# waga_can.net
KiCad netlist of a schematic drawn in EAGLE
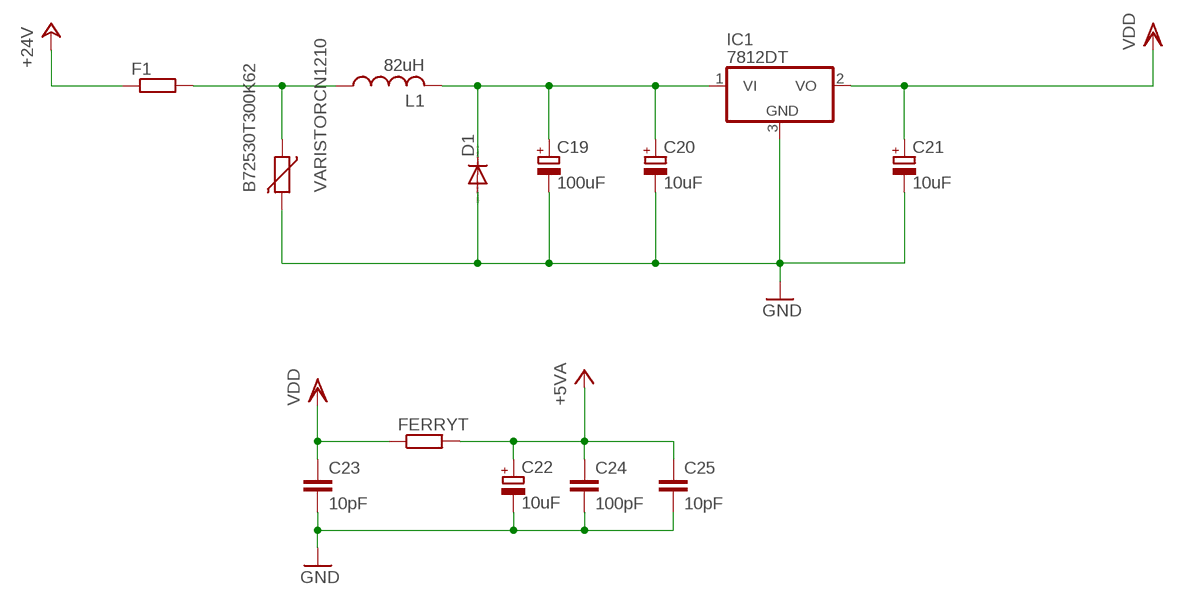
[diagram p0: schematic, sheet 1]
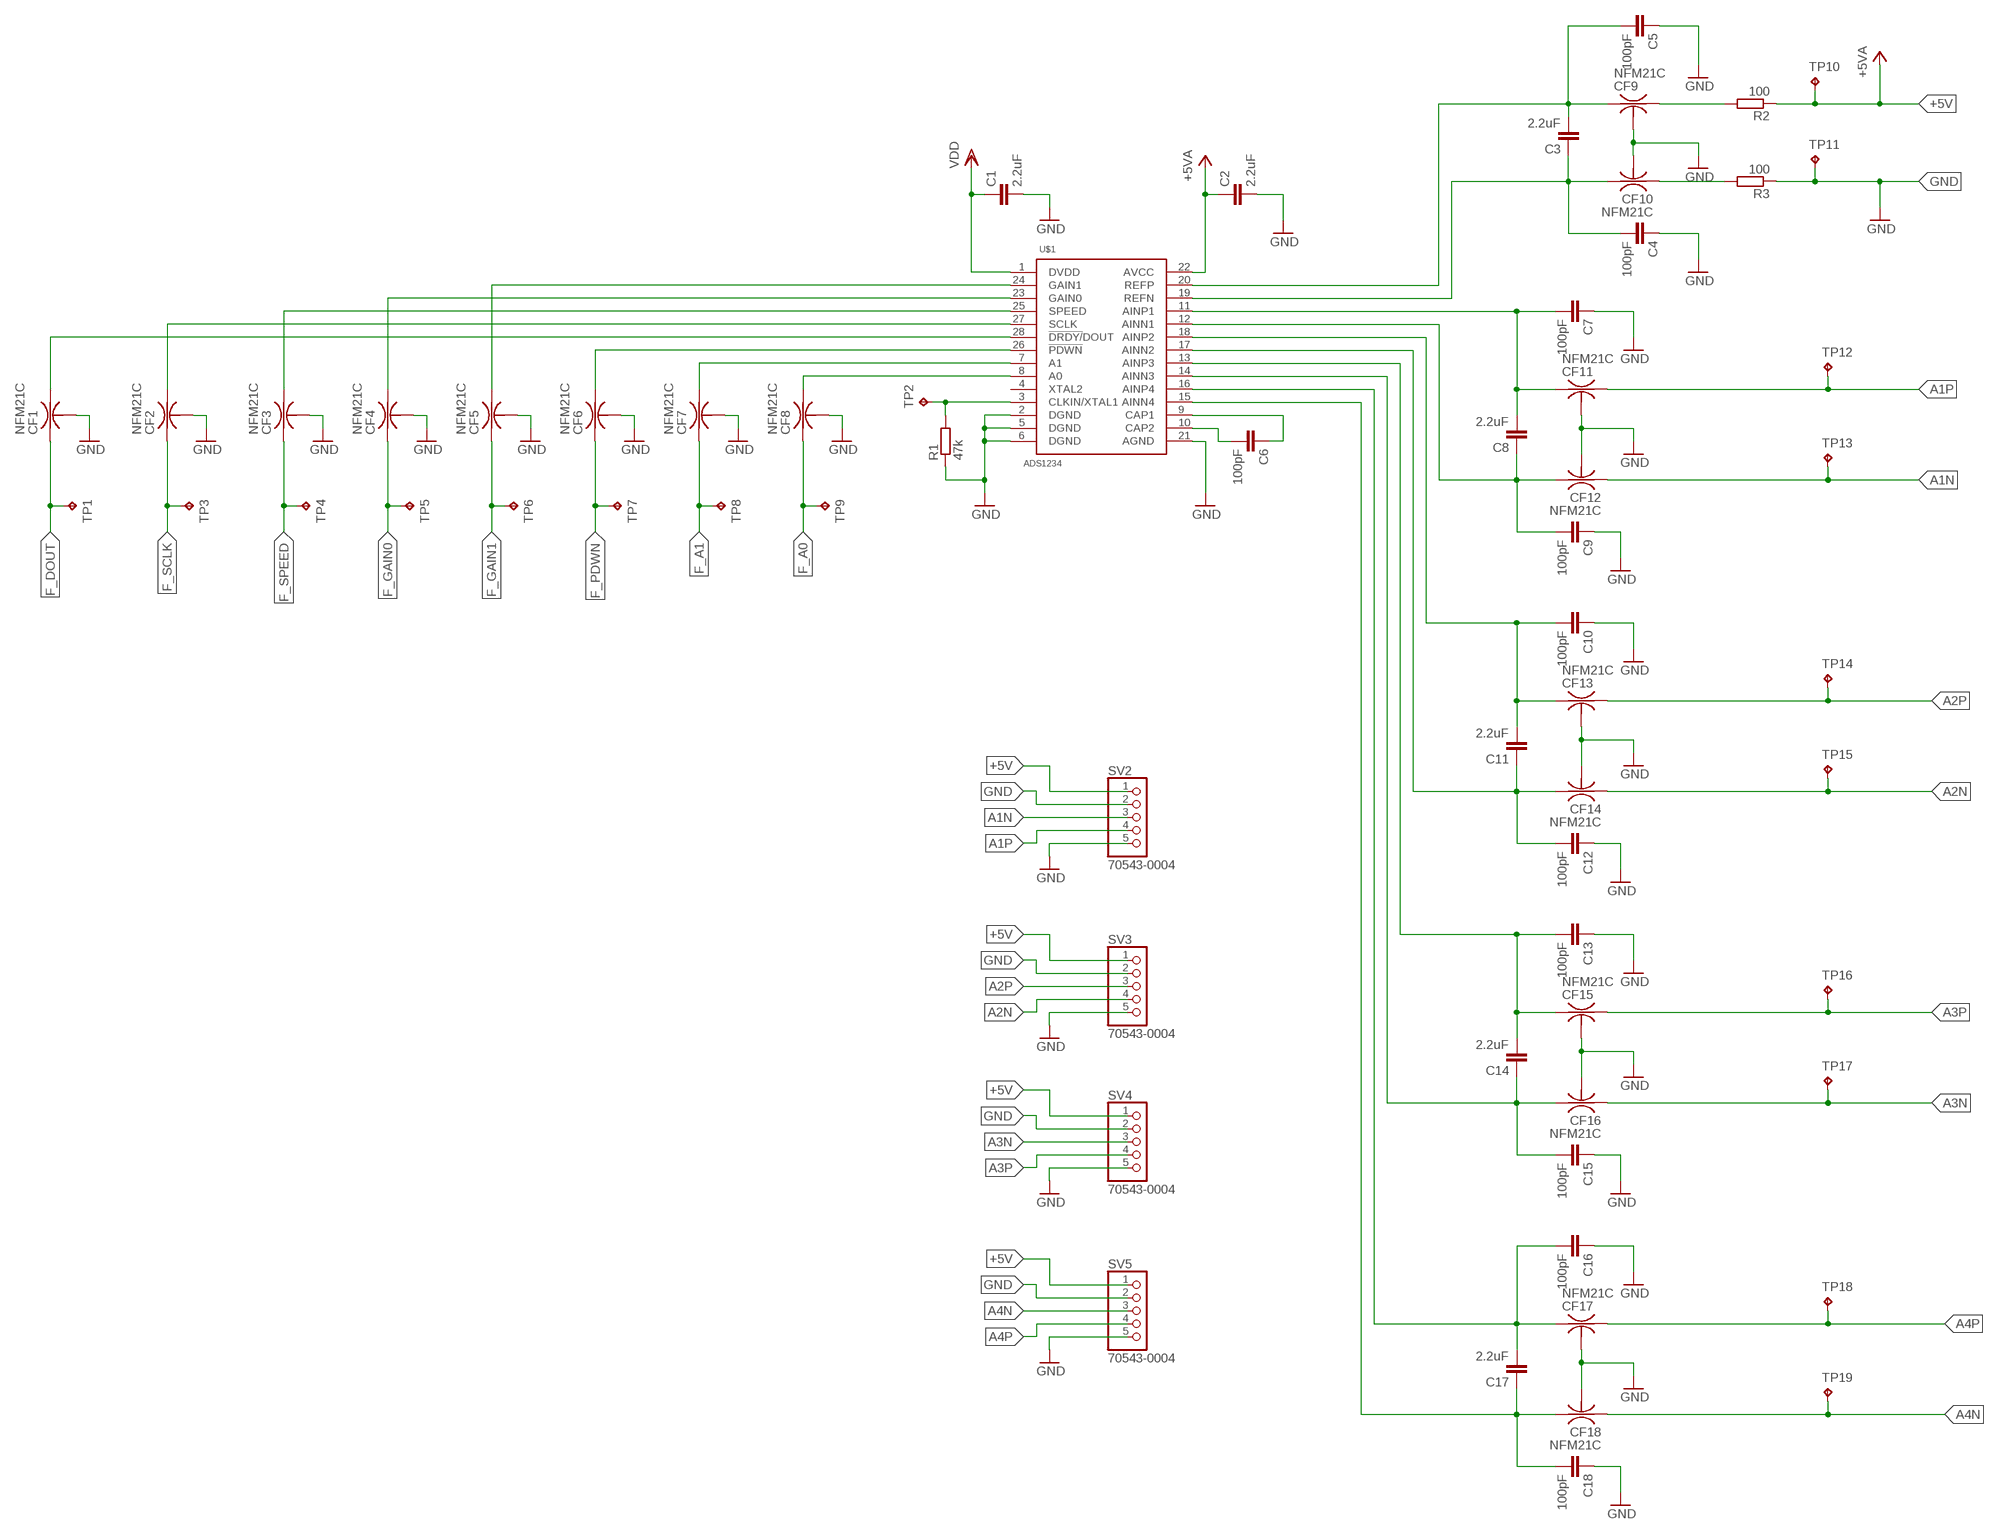
[diagram p1: schematic, sheet 2, part 1 of 2]
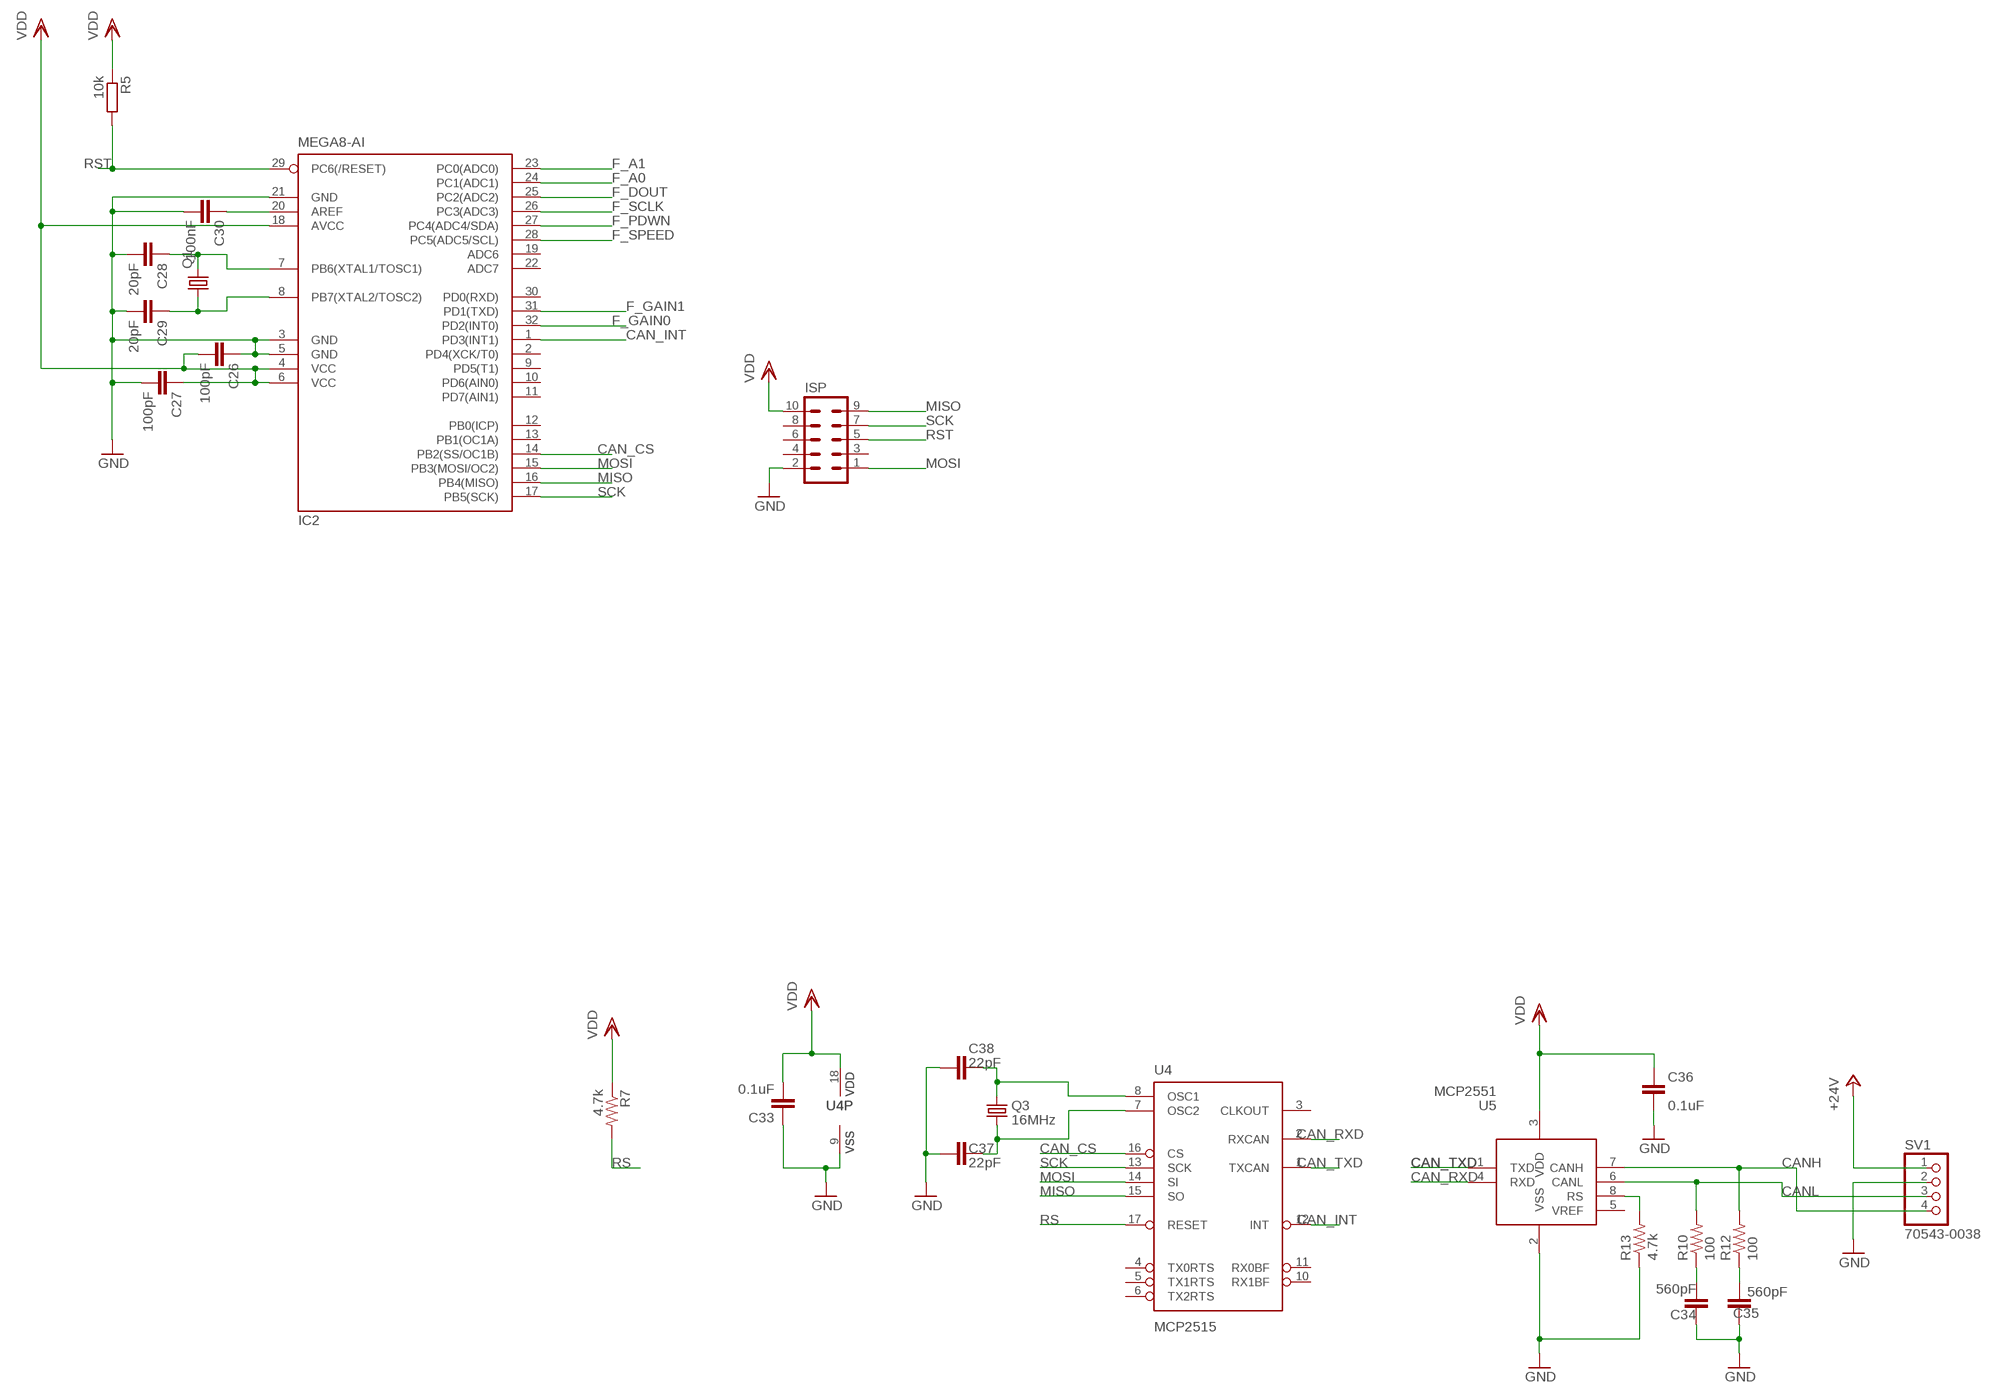
[diagram p2: schematic, sheet 2, part 2 of 2]

(export (version "E")
  (design (tool "Eeschema 10.0.6"))
  (components
    (comp (ref "C1")
      (value "2.2uF")
      (footprint "eagle-import:C0805K")
      (libsource (lib "eagle-import") (part "C-EUC0805K"))
    )
    (comp (ref "C2")
      (value "2.2uF")
      (footprint "eagle-import:C0805K")
      (libsource (lib "eagle-import") (part "C-EUC0805K"))
    )
    (comp (ref "C3")
      (value "2.2uF")
      (footprint "eagle-import:C0805K")
      (libsource (lib "eagle-import") (part "C-EUC0805K"))
    )
    (comp (ref "C4")
      (value "100pF")
      (footprint "eagle-import:C0805K")
      (libsource (lib "eagle-import") (part "C-EUC0805K"))
    )
    (comp (ref "C5")
      (value "100pF")
      (footprint "eagle-import:C0805K")
      (libsource (lib "eagle-import") (part "C-EUC0805K"))
    )
    (comp (ref "C6")
      (value "100pF")
      (footprint "eagle-import:C0805K")
      (libsource (lib "eagle-import") (part "C-EUC0805K"))
    )
    (comp (ref "C7")
      (value "100pF")
      (footprint "eagle-import:C0805K")
      (libsource (lib "eagle-import") (part "C-EUC0805K"))
    )
    (comp (ref "C8")
      (value "2.2uF")
      (footprint "eagle-import:C0805K")
      (libsource (lib "eagle-import") (part "C-EUC0805K"))
    )
    (comp (ref "C9")
      (value "100pF")
      (footprint "eagle-import:C0805K")
      (libsource (lib "eagle-import") (part "C-EUC0805K"))
    )
    (comp (ref "C10")
      (value "100pF")
      (footprint "eagle-import:C0805K")
      (libsource (lib "eagle-import") (part "C-EUC0805K"))
    )
    (comp (ref "C11")
      (value "2.2uF")
      (footprint "eagle-import:C0805K")
      (libsource (lib "eagle-import") (part "C-EUC0805K"))
    )
    (comp (ref "C12")
      (value "100pF")
      (footprint "eagle-import:C0805K")
      (libsource (lib "eagle-import") (part "C-EUC0805K"))
    )
    (comp (ref "C13")
      (value "100pF")
      (footprint "eagle-import:C0805K")
      (libsource (lib "eagle-import") (part "C-EUC0805K"))
    )
    (comp (ref "C14")
      (value "2.2uF")
      (footprint "eagle-import:C0805K")
      (libsource (lib "eagle-import") (part "C-EUC0805K"))
    )
    (comp (ref "C15")
      (value "100pF")
      (footprint "eagle-import:C0805K")
      (libsource (lib "eagle-import") (part "C-EUC0805K"))
    )
    (comp (ref "C16")
      (value "100pF")
      (footprint "eagle-import:C0805K")
      (libsource (lib "eagle-import") (part "C-EUC0805K"))
    )
    (comp (ref "C17")
      (value "2.2uF")
      (footprint "eagle-import:C0805K")
      (libsource (lib "eagle-import") (part "C-EUC0805K"))
    )
    (comp (ref "C18")
      (value "100pF")
      (footprint "eagle-import:C0805K")
      (libsource (lib "eagle-import") (part "C-EUC0805K"))
    )
    (comp (ref "C26")
      (value "100pF")
      (footprint "eagle-import:C0805K")
      (libsource (lib "eagle-import") (part "C-EUC0805K"))
    )
    (comp (ref "C27")
      (value "100pF")
      (footprint "eagle-import:C0805K")
      (libsource (lib "eagle-import") (part "C-EUC0805K"))
    )
    (comp (ref "C28")
      (value "20pF")
      (footprint "eagle-import:C0805K")
      (libsource (lib "eagle-import") (part "C-EUC0805K"))
    )
    (comp (ref "C29")
      (value "20pF")
      (footprint "eagle-import:C0805K")
      (libsource (lib "eagle-import") (part "C-EUC0805K"))
    )
    (comp (ref "C30")
      (value "100nF")
      (footprint "eagle-import:C0805K")
      (libsource (lib "eagle-import") (part "C-EUC0805K"))
    )
    (comp (ref "C33")
      (value "0.1uF")
      (footprint "eagle-import:0603-CAP")
      (libsource (lib "eagle-import") (part "CAP0603-CAP"))
    )
    (comp (ref "C34")
      (value "560pF")
      (footprint "eagle-import:0603-CAP")
      (libsource (lib "eagle-import") (part "CAP0603-CAP"))
    )
    (comp (ref "C35")
      (value "560pF")
      (footprint "eagle-import:0603-CAP")
      (libsource (lib "eagle-import") (part "CAP0603-CAP"))
    )
    (comp (ref "C36")
      (value "0.1uF")
      (footprint "eagle-import:0603-CAP")
      (libsource (lib "eagle-import") (part "CAP0603-CAP"))
    )
    (comp (ref "C37")
      (value "22pF")
      (footprint "eagle-import:0603-CAP")
      (libsource (lib "eagle-import") (part "CAP0603-CAP"))
    )
    (comp (ref "C38")
      (value "22pF")
      (footprint "eagle-import:0603-CAP")
      (libsource (lib "eagle-import") (part "CAP0603-CAP"))
    )
    (comp (ref "CF1")
      (value "NFM21C")
      (footprint "eagle-import:NFM21C")
      (fields (field (name "MPN") "NFM21CC102R1H3D"))
      (libsource (lib "eagle-import") (part "NFM21C"))
    )
    (comp (ref "CF2")
      (value "NFM21C")
      (footprint "eagle-import:NFM21C")
      (fields (field (name "MPN") "NFM21CC102R1H3D"))
      (libsource (lib "eagle-import") (part "NFM21C"))
    )
    (comp (ref "CF3")
      (value "NFM21C")
      (footprint "eagle-import:NFM21C")
      (fields (field (name "MPN") "NFM21CC102R1H3D"))
      (libsource (lib "eagle-import") (part "NFM21C"))
    )
    (comp (ref "CF4")
      (value "NFM21C")
      (footprint "eagle-import:NFM21C")
      (fields (field (name "MPN") "NFM21CC102R1H3D"))
      (libsource (lib "eagle-import") (part "NFM21C"))
    )
    (comp (ref "CF5")
      (value "NFM21C")
      (footprint "eagle-import:NFM21C")
      (fields (field (name "MPN") "NFM21CC102R1H3D"))
      (libsource (lib "eagle-import") (part "NFM21C"))
    )
    (comp (ref "CF6")
      (value "NFM21C")
      (footprint "eagle-import:NFM21C")
      (fields (field (name "MPN") "NFM21CC102R1H3D"))
      (libsource (lib "eagle-import") (part "NFM21C"))
    )
    (comp (ref "CF7")
      (value "NFM21C")
      (footprint "eagle-import:NFM21C")
      (fields (field (name "MPN") "NFM21CC102R1H3D"))
      (libsource (lib "eagle-import") (part "NFM21C"))
    )
    (comp (ref "CF8")
      (value "NFM21C")
      (footprint "eagle-import:NFM21C")
      (fields (field (name "MPN") "NFM21CC102R1H3D"))
      (libsource (lib "eagle-import") (part "NFM21C"))
    )
    (comp (ref "CF9")
      (value "NFM21C")
      (footprint "eagle-import:NFM21C")
      (fields (field (name "MPN") "NFM21CC102R1H3D"))
      (libsource (lib "eagle-import") (part "NFM21C"))
    )
    (comp (ref "CF10")
      (value "NFM21C")
      (footprint "eagle-import:NFM21C")
      (fields (field (name "MPN") "NFM21CC102R1H3D"))
      (libsource (lib "eagle-import") (part "NFM21C"))
    )
    (comp (ref "CF11")
      (value "NFM21C")
      (footprint "eagle-import:NFM21C")
      (fields (field (name "MPN") "NFM21CC102R1H3D"))
      (libsource (lib "eagle-import") (part "NFM21C"))
    )
    (comp (ref "CF12")
      (value "NFM21C")
      (footprint "eagle-import:NFM21C")
      (fields (field (name "MPN") "NFM21CC102R1H3D"))
      (libsource (lib "eagle-import") (part "NFM21C"))
    )
    (comp (ref "CF13")
      (value "NFM21C")
      (footprint "eagle-import:NFM21C")
      (fields (field (name "MPN") "NFM21CC102R1H3D"))
      (libsource (lib "eagle-import") (part "NFM21C"))
    )
    (comp (ref "CF14")
      (value "NFM21C")
      (footprint "eagle-import:NFM21C")
      (fields (field (name "MPN") "NFM21CC102R1H3D"))
      (libsource (lib "eagle-import") (part "NFM21C"))
    )
    (comp (ref "CF15")
      (value "NFM21C")
      (footprint "eagle-import:NFM21C")
      (fields (field (name "MPN") "NFM21CC102R1H3D"))
      (libsource (lib "eagle-import") (part "NFM21C"))
    )
    (comp (ref "CF16")
      (value "NFM21C")
      (footprint "eagle-import:NFM21C")
      (fields (field (name "MPN") "NFM21CC102R1H3D"))
      (libsource (lib "eagle-import") (part "NFM21C"))
    )
    (comp (ref "CF17")
      (value "NFM21C")
      (footprint "eagle-import:NFM21C")
      (fields (field (name "MPN") "NFM21CC102R1H3D"))
      (libsource (lib "eagle-import") (part "NFM21C"))
    )
    (comp (ref "CF18")
      (value "NFM21C")
      (footprint "eagle-import:NFM21C")
      (fields (field (name "MPN") "NFM21CC102R1H3D"))
      (libsource (lib "eagle-import") (part "NFM21C"))
    )
    (comp (ref "IC2")
      (value "MEGA8-AI")
      (footprint "eagle-import:TQFP32-08")
      (fields (field (name "MPN") "ATMEGA8-16AU"))
      (libsource (lib "eagle-import") (part "MEGA8-AI"))
    )
    (comp (ref "ISP")
      (value "ML10")
      (footprint "eagle-import:ML10")
      (libsource (lib "eagle-import") (part "ML10"))
    )
    (comp (ref "Q1")
      (value "CRYSTALCTS406")
      (footprint "eagle-import:CTS406")
      (libsource (lib "eagle-import") (part "CRYSTALCTS406"))
    )
    (comp (ref "Q3")
      (value "16MHz")
      (footprint "eagle-import:CRYSTAL-SMD-5X3")
      (libsource (lib "eagle-import") (part "CRYSTAL5X3"))
    )
    (comp (ref "R1")
      (value "47k")
      (footprint "eagle-import:R0805")
      (libsource (lib "eagle-import") (part "R-EU_R0805"))
    )
    (comp (ref "R2")
      (value "100")
      (footprint "eagle-import:R0805")
      (libsource (lib "eagle-import") (part "R-EU_R0805"))
    )
    (comp (ref "R3")
      (value "100")
      (footprint "eagle-import:R0805")
      (libsource (lib "eagle-import") (part "R-EU_R0805"))
    )
    (comp (ref "R5")
      (value "10k")
      (footprint "eagle-import:R0805")
      (libsource (lib "eagle-import") (part "R-EU_R0805"))
    )
    (comp (ref "R7")
      (value "4.7k")
      (footprint "eagle-import:0603-RES")
      (libsource (lib "eagle-import") (part "RESISTOR0603-RES"))
    )
    (comp (ref "R10")
      (value "100")
      (footprint "eagle-import:0603-RES")
      (libsource (lib "eagle-import") (part "RESISTOR0603-RES"))
    )
    (comp (ref "R12")
      (value "100")
      (footprint "eagle-import:0603-RES")
      (libsource (lib "eagle-import") (part "RESISTOR0603-RES"))
    )
    (comp (ref "R13")
      (value "4.7k")
      (footprint "eagle-import:0603-RES")
      (libsource (lib "eagle-import") (part "RESISTOR0603-RES"))
    )
    (comp (ref "SV1")
      (value "70543-0038")
      (footprint "eagle-import:70543-0038")
      (libsource (lib "eagle-import") (part "70543-0038"))
    )
    (comp (ref "SV2")
      (value "70543-0004")
      (footprint "eagle-import:70543-0004")
      (libsource (lib "eagle-import") (part "70543-0004"))
    )
    (comp (ref "SV3")
      (value "70543-0004")
      (footprint "eagle-import:70543-0004")
      (libsource (lib "eagle-import") (part "70543-0004"))
    )
    (comp (ref "SV4")
      (value "70543-0004")
      (footprint "eagle-import:70543-0004")
      (libsource (lib "eagle-import") (part "70543-0004"))
    )
    (comp (ref "SV5")
      (value "70543-0004")
      (footprint "eagle-import:70543-0004")
      (libsource (lib "eagle-import") (part "70543-0004"))
    )
    (comp (ref "TP1")
      (value "TPTP06R")
      (footprint "eagle-import:TP06R")
      (libsource (lib "eagle-import") (part "TPTP06R"))
    )
    (comp (ref "TP2")
      (value "TPTP06R")
      (footprint "eagle-import:TP06R")
      (libsource (lib "eagle-import") (part "TPTP06R"))
    )
    (comp (ref "TP3")
      (value "TPTP06R")
      (footprint "eagle-import:TP06R")
      (libsource (lib "eagle-import") (part "TPTP06R"))
    )
    (comp (ref "TP4")
      (value "TPTP06R")
      (footprint "eagle-import:TP06R")
      (libsource (lib "eagle-import") (part "TPTP06R"))
    )
    (comp (ref "TP5")
      (value "TPTP06R")
      (footprint "eagle-import:TP06R")
      (libsource (lib "eagle-import") (part "TPTP06R"))
    )
    (comp (ref "TP6")
      (value "TPTP06R")
      (footprint "eagle-import:TP06R")
      (libsource (lib "eagle-import") (part "TPTP06R"))
    )
    (comp (ref "TP7")
      (value "TPTP06R")
      (footprint "eagle-import:TP06R")
      (libsource (lib "eagle-import") (part "TPTP06R"))
    )
    (comp (ref "TP8")
      (value "TPTP06R")
      (footprint "eagle-import:TP06R")
      (libsource (lib "eagle-import") (part "TPTP06R"))
    )
    (comp (ref "TP9")
      (value "TPTP06R")
      (footprint "eagle-import:TP06R")
      (libsource (lib "eagle-import") (part "TPTP06R"))
    )
    (comp (ref "TP10")
      (value "TPTP06R")
      (footprint "eagle-import:TP06R")
      (libsource (lib "eagle-import") (part "TPTP06R"))
    )
    (comp (ref "TP11")
      (value "TPTP06R")
      (footprint "eagle-import:TP06R")
      (libsource (lib "eagle-import") (part "TPTP06R"))
    )
    (comp (ref "TP12")
      (value "TPTP06R")
      (footprint "eagle-import:TP06R")
      (libsource (lib "eagle-import") (part "TPTP06R"))
    )
    (comp (ref "TP13")
      (value "TPTP06R")
      (footprint "eagle-import:TP06R")
      (libsource (lib "eagle-import") (part "TPTP06R"))
    )
    (comp (ref "TP14")
      (value "TPTP06R")
      (footprint "eagle-import:TP06R")
      (libsource (lib "eagle-import") (part "TPTP06R"))
    )
    (comp (ref "TP15")
      (value "TPTP06R")
      (footprint "eagle-import:TP06R")
      (libsource (lib "eagle-import") (part "TPTP06R"))
    )
    (comp (ref "TP16")
      (value "TPTP06R")
      (footprint "eagle-import:TP06R")
      (libsource (lib "eagle-import") (part "TPTP06R"))
    )
    (comp (ref "TP17")
      (value "TPTP06R")
      (footprint "eagle-import:TP06R")
      (libsource (lib "eagle-import") (part "TPTP06R"))
    )
    (comp (ref "TP18")
      (value "TPTP06R")
      (footprint "eagle-import:TP06R")
      (libsource (lib "eagle-import") (part "TPTP06R"))
    )
    (comp (ref "TP19")
      (value "TPTP06R")
      (footprint "eagle-import:TP06R")
      (libsource (lib "eagle-import") (part "TPTP06R"))
    )
    (comp (ref "U$1")
      (value "ADS1234")
      (footprint "eagle-import:TSSOP-28")
      (libsource (lib "eagle-import") (part "ADS1234"))
    )
    (comp (ref "U4")
      (value "MCP2515")
      (footprint "eagle-import:SO-18W")
      (libsource (lib "eagle-import") (part "MCP2510SO"))
    )
    (comp (ref "U5")
      (value "MCP2551")
      (footprint "eagle-import:SO-08M")
      (libsource (lib "eagle-import") (part "MCP2551"))
    )
    (comp (ref "B72530T300K62")
      (value "VARISTORCN1210")
      (footprint "eagle-import:CT_CN1210")
      (libsource (lib "eagle-import") (part "VARISTORCN1210"))
    )
    (comp (ref "C19")
      (value "100uF")
      (footprint "eagle-import:153CLV-0810")
      (libsource (lib "eagle-import") (part "CPOL-EU153CLV-0810"))
    )
    (comp (ref "C20")
      (value "10uF")
      (footprint "eagle-import:153CLV-0605")
      (libsource (lib "eagle-import") (part "CPOL-EU153CLV-0605"))
    )
    (comp (ref "C21")
      (value "10uF")
      (footprint "eagle-import:153CLV-0605")
      (libsource (lib "eagle-import") (part "CPOL-EU153CLV-0605"))
    )
    (comp (ref "C22")
      (value "10uF")
      (footprint "eagle-import:153CLV-0605")
      (libsource (lib "eagle-import") (part "CPOL-EU153CLV-0605"))
    )
    (comp (ref "C23")
      (value "10pF")
      (footprint "eagle-import:C0805")
      (libsource (lib "eagle-import") (part "C-EUC0805"))
    )
    (comp (ref "C24")
      (value "100pF")
      (footprint "eagle-import:C0805")
      (libsource (lib "eagle-import") (part "C-EUC0805"))
    )
    (comp (ref "C25")
      (value "10pF")
      (footprint "eagle-import:C0805")
      (libsource (lib "eagle-import") (part "C-EUC0805"))
    )
    (comp (ref "D1")
      (value "DIODE-SMB")
      (footprint "eagle-import:SMB")
      (libsource (lib "eagle-import") (part "DIODE-SMB"))
    )
    (comp (ref "F1")
      (value "R-EU_1812X7R")
      (footprint "eagle-import:1812X7R")
      (libsource (lib "eagle-import") (part "R-EU_1812X7R"))
    )
    (comp (ref "FERRYT")
      (value "R-EU_M0805")
      (footprint "eagle-import:M0805")
      (libsource (lib "eagle-import") (part "R-EU_M0805"))
    )
    (comp (ref "IC1")
      (value "7812DT")
      (footprint "eagle-import:TO252")
      (libsource (lib "eagle-import") (part "78DT12"))
    )
    (comp (ref "L1")
      (value "82uH")
      (footprint "eagle-import:L4532P")
      (libsource (lib "eagle-import") (part "L-USL4532P"))
    )
  )
  (nets
    (net (code "1") (name "+5V") (class "Default")
      (node (ref "C2") (pin "1") (pinfunction "1_1") (pintype "passive"))
      (node (ref "C22") (pin "+") (pinfunction "+_+") (pintype "passive"))
      (node (ref "C24") (pin "1") (pinfunction "1_1") (pintype "passive"))
      (node (ref "C25") (pin "1") (pinfunction "1_1") (pintype "passive"))
      (node (ref "FERRYT") (pin "2") (pinfunction "2_2") (pintype "passive"))
      (node (ref "R2") (pin "1") (pinfunction "1_1") (pintype "passive"))
      (node (ref "SV2") (pin "1") (pinfunction "1_1") (pintype "passive"))
      (node (ref "SV3") (pin "1") (pinfunction "1_1") (pintype "passive"))
      (node (ref "SV4") (pin "1") (pinfunction "1_1") (pintype "passive"))
      (node (ref "SV5") (pin "1") (pinfunction "1_1") (pintype "passive"))
      (node (ref "TP10") (pin "TP") (pinfunction "TP_TP") (pintype "input"))
      (node (ref "U$1") (pin "22") (pinfunction "AVCC_22") (pintype "bidirectional"))
    )
    (net (code "2") (name "+24V") (class "Default")
      (node (ref "F1") (pin "1") (pinfunction "1_1") (pintype "passive"))
      (node (ref "SV1") (pin "1") (pinfunction "1_1") (pintype "passive"))
    )
    (net (code "3") (name "A1N") (class "Default")
      (node (ref "CF12") (pin "1") (pinfunction "1_1") (pintype "passive"))
      (node (ref "SV2") (pin "3") (pinfunction "3_3") (pintype "passive"))
      (node (ref "TP13") (pin "TP") (pinfunction "TP_TP") (pintype "input"))
    )
    (net (code "4") (name "A1P") (class "Default")
      (node (ref "CF11") (pin "3") (pinfunction "3_3") (pintype "passive"))
      (node (ref "SV2") (pin "4") (pinfunction "4_4") (pintype "passive"))
      (node (ref "TP12") (pin "TP") (pinfunction "TP_TP") (pintype "input"))
    )
    (net (code "5") (name "A2N") (class "Default")
      (node (ref "CF14") (pin "1") (pinfunction "1_1") (pintype "passive"))
      (node (ref "SV3") (pin "4") (pinfunction "4_4") (pintype "passive"))
      (node (ref "TP15") (pin "TP") (pinfunction "TP_TP") (pintype "input"))
    )
    (net (code "6") (name "A2P") (class "Default")
      (node (ref "CF13") (pin "3") (pinfunction "3_3") (pintype "passive"))
      (node (ref "SV3") (pin "3") (pinfunction "3_3") (pintype "passive"))
      (node (ref "TP14") (pin "TP") (pinfunction "TP_TP") (pintype "input"))
    )
    (net (code "7") (name "A3N") (class "Default")
      (node (ref "CF16") (pin "1") (pinfunction "1_1") (pintype "passive"))
      (node (ref "SV4") (pin "3") (pinfunction "3_3") (pintype "passive"))
      (node (ref "TP17") (pin "TP") (pinfunction "TP_TP") (pintype "input"))
    )
    (net (code "8") (name "A3P") (class "Default")
      (node (ref "CF15") (pin "3") (pinfunction "3_3") (pintype "passive"))
      (node (ref "SV4") (pin "4") (pinfunction "4_4") (pintype "passive"))
      (node (ref "TP16") (pin "TP") (pinfunction "TP_TP") (pintype "input"))
    )
    (net (code "9") (name "A4N") (class "Default")
      (node (ref "CF18") (pin "1") (pinfunction "1_1") (pintype "passive"))
      (node (ref "SV5") (pin "3") (pinfunction "3_3") (pintype "passive"))
      (node (ref "TP19") (pin "TP") (pinfunction "TP_TP") (pintype "input"))
    )
    (net (code "10") (name "A4P") (class "Default")
      (node (ref "CF17") (pin "3") (pinfunction "3_3") (pintype "passive"))
      (node (ref "SV5") (pin "4") (pinfunction "4_4") (pintype "passive"))
      (node (ref "TP18") (pin "TP") (pinfunction "TP_TP") (pintype "input"))
    )
    (net (code "11") (name "CANH") (class "Default")
      (node (ref "R12") (pin "2") (pinfunction "2_2") (pintype "passive"))
      (node (ref "SV1") (pin "4") (pinfunction "4_4") (pintype "passive"))
      (node (ref "U5") (pin "7") (pinfunction "CANH_7") (pintype "bidirectional"))
    )
    (net (code "12") (name "CANL") (class "Default")
      (node (ref "R10") (pin "2") (pinfunction "2_2") (pintype "passive"))
      (node (ref "SV1") (pin "3") (pinfunction "3_3") (pintype "passive"))
      (node (ref "U5") (pin "6") (pinfunction "CANL_6") (pintype "bidirectional"))
    )
    (net (code "13") (name "CAN_CS") (class "Default")
      (node (ref "IC2") (pin "14") (pinfunction "PB2(SS/OC1B)_14") (pintype "bidirectional"))
      (node (ref "U4") (pin "16") (pinfunction "CS_16") (pintype "input"))
    )
    (net (code "14") (name "CAN_INT") (class "Default")
      (node (ref "IC2") (pin "1") (pinfunction "PD3(INT1)_1") (pintype "bidirectional"))
      (node (ref "U4") (pin "12") (pinfunction "INT_12") (pintype "output"))
    )
    (net (code "15") (name "CAN_RXD") (class "Default")
      (node (ref "U4") (pin "2") (pinfunction "RXCAN_2") (pintype "input"))
      (node (ref "U5") (pin "4") (pinfunction "RXD_4") (pintype "bidirectional"))
    )
    (net (code "16") (name "CAN_TXD") (class "Default")
      (node (ref "U4") (pin "1") (pinfunction "TXCAN_1") (pintype "output"))
      (node (ref "U5") (pin "1") (pinfunction "TXD_1") (pintype "bidirectional"))
    )
    (net (code "17") (name "F_A0") (class "Default")
      (node (ref "CF8") (pin "1") (pinfunction "1_1") (pintype "passive"))
      (node (ref "IC2") (pin "24") (pinfunction "PC1(ADC1)_24") (pintype "bidirectional"))
      (node (ref "TP9") (pin "TP") (pinfunction "TP_TP") (pintype "input"))
    )
    (net (code "18") (name "F_A1") (class "Default")
      (node (ref "CF7") (pin "1") (pinfunction "1_1") (pintype "passive"))
      (node (ref "IC2") (pin "23") (pinfunction "PC0(ADC0)_23") (pintype "bidirectional"))
      (node (ref "TP8") (pin "TP") (pinfunction "TP_TP") (pintype "input"))
    )
    (net (code "19") (name "F_DOUT") (class "Default")
      (node (ref "CF1") (pin "1") (pinfunction "1_1") (pintype "passive"))
      (node (ref "IC2") (pin "25") (pinfunction "PC2(ADC2)_25") (pintype "bidirectional"))
      (node (ref "TP1") (pin "TP") (pinfunction "TP_TP") (pintype "input"))
    )
    (net (code "20") (name "F_GAIN0") (class "Default")
      (node (ref "CF4") (pin "1") (pinfunction "1_1") (pintype "passive"))
      (node (ref "IC2") (pin "32") (pinfunction "PD2(INT0)_32") (pintype "bidirectional"))
      (node (ref "TP5") (pin "TP") (pinfunction "TP_TP") (pintype "input"))
    )
    (net (code "21") (name "F_GAIN1") (class "Default")
      (node (ref "CF5") (pin "1") (pinfunction "1_1") (pintype "passive"))
      (node (ref "IC2") (pin "31") (pinfunction "PD1(TXD)_31") (pintype "bidirectional"))
      (node (ref "TP6") (pin "TP") (pinfunction "TP_TP") (pintype "input"))
    )
    (net (code "22") (name "F_PDWN") (class "Default")
      (node (ref "CF6") (pin "1") (pinfunction "1_1") (pintype "passive"))
      (node (ref "IC2") (pin "27") (pinfunction "PC4(ADC4/SDA)_27") (pintype "bidirectional"))
      (node (ref "TP7") (pin "TP") (pinfunction "TP_TP") (pintype "input"))
    )
    (net (code "23") (name "F_SCLK") (class "Default")
      (node (ref "CF2") (pin "1") (pinfunction "1_1") (pintype "passive"))
      (node (ref "IC2") (pin "26") (pinfunction "PC3(ADC3)_26") (pintype "bidirectional"))
      (node (ref "TP3") (pin "TP") (pinfunction "TP_TP") (pintype "input"))
    )
    (net (code "24") (name "F_SPEED") (class "Default")
      (node (ref "CF3") (pin "1") (pinfunction "1_1") (pintype "passive"))
      (node (ref "IC2") (pin "28") (pinfunction "PC5(ADC5/SCL)_28") (pintype "bidirectional"))
      (node (ref "TP4") (pin "TP") (pinfunction "TP_TP") (pintype "input"))
    )
    (net (code "25") (name "GND") (class "Default")
      (node (ref "B72530T300K62") (pin "2") (pinfunction "2_2") (pintype "passive"))
      (node (ref "C1") (pin "2") (pinfunction "2_2") (pintype "passive"))
      (node (ref "C10") (pin "1") (pinfunction "1_1") (pintype "passive"))
      (node (ref "C12") (pin "1") (pinfunction "1_1") (pintype "passive"))
      (node (ref "C13") (pin "1") (pinfunction "1_1") (pintype "passive"))
      (node (ref "C15") (pin "1") (pinfunction "1_1") (pintype "passive"))
      (node (ref "C16") (pin "1") (pinfunction "1_1") (pintype "passive"))
      (node (ref "C18") (pin "1") (pinfunction "1_1") (pintype "passive"))
      (node (ref "C19") (pin "-") (pinfunction "-_-") (pintype "passive"))
      (node (ref "C2") (pin "2") (pinfunction "2_2") (pintype "passive"))
      (node (ref "C20") (pin "-") (pinfunction "-_-") (pintype "passive"))
      (node (ref "C21") (pin "-") (pinfunction "-_-") (pintype "passive"))
      (node (ref "C22") (pin "-") (pinfunction "-_-") (pintype "passive"))
      (node (ref "C23") (pin "2") (pinfunction "2_2") (pintype "passive"))
      (node (ref "C24") (pin "2") (pinfunction "2_2") (pintype "passive"))
      (node (ref "C25") (pin "2") (pinfunction "2_2") (pintype "passive"))
      (node (ref "C26") (pin "1") (pinfunction "1_1") (pintype "passive"))
      (node (ref "C27") (pin "2") (pinfunction "2_2") (pintype "passive"))
      (node (ref "C28") (pin "2") (pinfunction "2_2") (pintype "passive"))
      (node (ref "C29") (pin "2") (pinfunction "2_2") (pintype "passive"))
      (node (ref "C30") (pin "2") (pinfunction "2_2") (pintype "passive"))
      (node (ref "C33") (pin "1") (pinfunction "1_1") (pintype "passive"))
      (node (ref "C34") (pin "1") (pinfunction "1_1") (pintype "passive"))
      (node (ref "C35") (pin "1") (pinfunction "1_1") (pintype "passive"))
      (node (ref "C36") (pin "1") (pinfunction "1_1") (pintype "passive"))
      (node (ref "C37") (pin "1") (pinfunction "1_1") (pintype "passive"))
      (node (ref "C38") (pin "1") (pinfunction "1_1") (pintype "passive"))
      (node (ref "C4") (pin "1") (pinfunction "1_1") (pintype "passive"))
      (node (ref "C5") (pin "1") (pinfunction "1_1") (pintype "passive"))
      (node (ref "C7") (pin "1") (pinfunction "1_1") (pintype "passive"))
      (node (ref "C9") (pin "1") (pinfunction "1_1") (pintype "passive"))
      (node (ref "CF1") (pin "2@1") (pinfunction "2_2@1") (pintype "passive"))
      (node (ref "CF1") (pin "2@2") (pinfunction "2_2@2") (pintype "passive"))
      (node (ref "CF10") (pin "2@1") (pinfunction "2_2@1") (pintype "passive"))
      (node (ref "CF10") (pin "2@2") (pinfunction "2_2@2") (pintype "passive"))
      (node (ref "CF11") (pin "2@1") (pinfunction "2_2@1") (pintype "passive"))
      (node (ref "CF11") (pin "2@2") (pinfunction "2_2@2") (pintype "passive"))
      (node (ref "CF12") (pin "2@1") (pinfunction "2_2@1") (pintype "passive"))
      (node (ref "CF12") (pin "2@2") (pinfunction "2_2@2") (pintype "passive"))
      (node (ref "CF13") (pin "2@1") (pinfunction "2_2@1") (pintype "passive"))
      (node (ref "CF13") (pin "2@2") (pinfunction "2_2@2") (pintype "passive"))
      (node (ref "CF14") (pin "2@1") (pinfunction "2_2@1") (pintype "passive"))
      (node (ref "CF14") (pin "2@2") (pinfunction "2_2@2") (pintype "passive"))
      (node (ref "CF15") (pin "2@1") (pinfunction "2_2@1") (pintype "passive"))
      (node (ref "CF15") (pin "2@2") (pinfunction "2_2@2") (pintype "passive"))
      (node (ref "CF16") (pin "2@1") (pinfunction "2_2@1") (pintype "passive"))
      (node (ref "CF16") (pin "2@2") (pinfunction "2_2@2") (pintype "passive"))
      (node (ref "CF17") (pin "2@1") (pinfunction "2_2@1") (pintype "passive"))
      (node (ref "CF17") (pin "2@2") (pinfunction "2_2@2") (pintype "passive"))
      (node (ref "CF18") (pin "2@1") (pinfunction "2_2@1") (pintype "passive"))
      (node (ref "CF18") (pin "2@2") (pinfunction "2_2@2") (pintype "passive"))
      (node (ref "CF2") (pin "2@1") (pinfunction "2_2@1") (pintype "passive"))
      (node (ref "CF2") (pin "2@2") (pinfunction "2_2@2") (pintype "passive"))
      (node (ref "CF3") (pin "2@1") (pinfunction "2_2@1") (pintype "passive"))
      (node (ref "CF3") (pin "2@2") (pinfunction "2_2@2") (pintype "passive"))
      (node (ref "CF4") (pin "2@1") (pinfunction "2_2@1") (pintype "passive"))
      (node (ref "CF4") (pin "2@2") (pinfunction "2_2@2") (pintype "passive"))
      (node (ref "CF5") (pin "2@1") (pinfunction "2_2@1") (pintype "passive"))
      (node (ref "CF5") (pin "2@2") (pinfunction "2_2@2") (pintype "passive"))
      (node (ref "CF6") (pin "2@1") (pinfunction "2_2@1") (pintype "passive"))
      (node (ref "CF6") (pin "2@2") (pinfunction "2_2@2") (pintype "passive"))
      (node (ref "CF7") (pin "2@1") (pinfunction "2_2@1") (pintype "passive"))
      (node (ref "CF7") (pin "2@2") (pinfunction "2_2@2") (pintype "passive"))
      (node (ref "CF8") (pin "2@1") (pinfunction "2_2@1") (pintype "passive"))
      (node (ref "CF8") (pin "2@2") (pinfunction "2_2@2") (pintype "passive"))
      (node (ref "CF9") (pin "2@1") (pinfunction "2_2@1") (pintype "passive"))
      (node (ref "CF9") (pin "2@2") (pinfunction "2_2@2") (pintype "passive"))
      (node (ref "D1") (pin "A") (pinfunction "A_A") (pintype "passive"))
      (node (ref "IC1") (pin "3") (pinfunction "GND_3") (pintype "passive"))
      (node (ref "IC2") (pin "21") (pinfunction "GND_21") (pintype "power_in"))
      (node (ref "IC2") (pin "3") (pinfunction "GND_3") (pintype "power_in"))
      (node (ref "IC2") (pin "5") (pinfunction "GND_5") (pintype "power_in"))
      (node (ref "ISP") (pin "2") (pinfunction "2_2") (pintype "passive"))
      (node (ref "R1") (pin "1") (pinfunction "1_1") (pintype "passive"))
      (node (ref "R13") (pin "1") (pinfunction "1_1") (pintype "passive"))
      (node (ref "R3") (pin "1") (pinfunction "1_1") (pintype "passive"))
      (node (ref "SV1") (pin "2") (pinfunction "2_2") (pintype "passive"))
      (node (ref "SV2") (pin "2") (pinfunction "2_2") (pintype "passive"))
      (node (ref "SV2") (pin "5") (pinfunction "5_5") (pintype "passive"))
      (node (ref "SV3") (pin "2") (pinfunction "2_2") (pintype "passive"))
      (node (ref "SV3") (pin "5") (pinfunction "5_5") (pintype "passive"))
      (node (ref "SV4") (pin "2") (pinfunction "2_2") (pintype "passive"))
      (node (ref "SV4") (pin "5") (pinfunction "5_5") (pintype "passive"))
      (node (ref "SV5") (pin "2") (pinfunction "2_2") (pintype "passive"))
      (node (ref "SV5") (pin "5") (pinfunction "5_5") (pintype "passive"))
      (node (ref "TP11") (pin "TP") (pinfunction "TP_TP") (pintype "input"))
      (node (ref "U$1") (pin "2") (pinfunction "DGND_2") (pintype "bidirectional"))
      (node (ref "U$1") (pin "21") (pinfunction "AGND_21") (pintype "bidirectional"))
      (node (ref "U$1") (pin "5") (pinfunction "DGND_5") (pintype "bidirectional"))
      (node (ref "U$1") (pin "6") (pinfunction "DGND_6") (pintype "bidirectional"))
      (node (ref "U4") (pin "9") (pinfunction "VSS_9") (pintype "power_in"))
      (node (ref "U5") (pin "2") (pinfunction "VSS_2") (pintype "power_in"))
    )
    (net (code "26") (name "MISO") (class "Default")
      (node (ref "IC2") (pin "16") (pinfunction "PB4(MISO)_16") (pintype "bidirectional"))
      (node (ref "ISP") (pin "9") (pinfunction "9_9") (pintype "passive"))
      (node (ref "U4") (pin "15") (pinfunction "SO_15") (pintype "output"))
    )
    (net (code "27") (name "MOSI") (class "Default")
      (node (ref "IC2") (pin "15") (pinfunction "PB3(MOSI/OC2)_15") (pintype "bidirectional"))
      (node (ref "ISP") (pin "1") (pinfunction "1_1") (pintype "passive"))
      (node (ref "U4") (pin "14") (pinfunction "SI_14") (pintype "input"))
    )
    (net (code "28") (name "Net-(B72530T300K62-Pad1)") (class "Default")
      (node (ref "B72530T300K62") (pin "1") (pinfunction "1_1") (pintype "passive"))
      (node (ref "F1") (pin "2") (pinfunction "2_2") (pintype "passive"))
      (node (ref "L1") (pin "1") (pinfunction "1_1") (pintype "passive"))
    )
    (net (code "29") (name "Net-(C34-Pad2)") (class "Default")
      (node (ref "C34") (pin "2") (pinfunction "2_2") (pintype "passive"))
      (node (ref "R10") (pin "1") (pinfunction "1_1") (pintype "passive"))
    )
    (net (code "30") (name "Net-(C35-Pad2)") (class "Default")
      (node (ref "C35") (pin "2") (pinfunction "2_2") (pintype "passive"))
      (node (ref "R12") (pin "1") (pinfunction "1_1") (pintype "passive"))
    )
    (net (code "31") (name "Net-(CF9-Pad3)") (class "Default")
      (node (ref "CF9") (pin "3") (pinfunction "3_3") (pintype "passive"))
      (node (ref "R2") (pin "2") (pinfunction "2_2") (pintype "passive"))
    )
    (net (code "32") (name "Net-(CF10-Pad1)") (class "Default")
      (node (ref "CF10") (pin "1") (pinfunction "1_1") (pintype "passive"))
      (node (ref "R3") (pin "2") (pinfunction "2_2") (pintype "passive"))
    )
    (net (code "33") (name "Net-(IC1-VI)") (class "Default")
      (node (ref "C19") (pin "+") (pinfunction "+_+") (pintype "passive"))
      (node (ref "C20") (pin "+") (pinfunction "+_+") (pintype "passive"))
      (node (ref "D1") (pin "C") (pinfunction "C_C") (pintype "passive"))
      (node (ref "IC1") (pin "1") (pinfunction "VI_1") (pintype "input"))
      (node (ref "L1") (pin "2") (pinfunction "2_2") (pintype "passive"))
    )
    (net (code "34") (name "Net-(IC2-AREF)") (class "Default")
      (node (ref "C30") (pin "1") (pinfunction "1_1") (pintype "passive"))
      (node (ref "IC2") (pin "20") (pinfunction "AREF_20") (pintype "passive"))
    )
    (net (code "35") (name "Net-(IC2-PB6(XTAL1{slash}TOSC1))") (class "Default")
      (node (ref "C28") (pin "1") (pinfunction "1_1") (pintype "passive"))
      (node (ref "IC2") (pin "7") (pinfunction "PB6(XTAL1/TOSC1)_7") (pintype "bidirectional"))
      (node (ref "Q1") (pin "3") (pinfunction "2_3") (pintype "passive"))
    )
    (net (code "36") (name "Net-(IC2-PB7(XTAL2{slash}TOSC2))") (class "Default")
      (node (ref "C29") (pin "1") (pinfunction "1_1") (pintype "passive"))
      (node (ref "IC2") (pin "8") (pinfunction "PB7(XTAL2/TOSC2)_8") (pintype "bidirectional"))
      (node (ref "Q1") (pin "1") (pinfunction "1_1") (pintype "passive"))
    )
    (net (code "37") (name "Net-(Q3-2)") (class "Default")
      (node (ref "C38") (pin "2") (pinfunction "2_2") (pintype "passive"))
      (node (ref "Q3") (pin "3") (pinfunction "2_3") (pintype "passive"))
      (node (ref "U4") (pin "8") (pinfunction "OSC1_8") (pintype "input"))
    )
    (net (code "38") (name "Net-(U$1-A0)") (class "Default")
      (node (ref "CF8") (pin "3") (pinfunction "3_3") (pintype "passive"))
      (node (ref "U$1") (pin "8") (pinfunction "A0_8") (pintype "bidirectional"))
    )
    (net (code "39") (name "Net-(U$1-A1)") (class "Default")
      (node (ref "CF7") (pin "3") (pinfunction "3_3") (pintype "passive"))
      (node (ref "U$1") (pin "7") (pinfunction "A1_7") (pintype "bidirectional"))
    )
    (net (code "40") (name "Net-(U$1-AINN1)") (class "Default")
      (node (ref "C8") (pin "1") (pinfunction "1_1") (pintype "passive"))
      (node (ref "C9") (pin "2") (pinfunction "2_2") (pintype "passive"))
      (node (ref "CF12") (pin "3") (pinfunction "3_3") (pintype "passive"))
      (node (ref "U$1") (pin "12") (pinfunction "AINN1_12") (pintype "bidirectional"))
    )
    (net (code "41") (name "Net-(U$1-AINN2)") (class "Default")
      (node (ref "C11") (pin "1") (pinfunction "1_1") (pintype "passive"))
      (node (ref "C12") (pin "2") (pinfunction "2_2") (pintype "passive"))
      (node (ref "CF14") (pin "3") (pinfunction "3_3") (pintype "passive"))
      (node (ref "U$1") (pin "17") (pinfunction "AINN2_17") (pintype "bidirectional"))
    )
    (net (code "42") (name "Net-(U$1-AINN3)") (class "Default")
      (node (ref "C14") (pin "1") (pinfunction "1_1") (pintype "passive"))
      (node (ref "C15") (pin "2") (pinfunction "2_2") (pintype "passive"))
      (node (ref "CF16") (pin "3") (pinfunction "3_3") (pintype "passive"))
      (node (ref "U$1") (pin "14") (pinfunction "AINN3_14") (pintype "bidirectional"))
    )
    (net (code "43") (name "Net-(U$1-AINN4)") (class "Default")
      (node (ref "C17") (pin "1") (pinfunction "1_1") (pintype "passive"))
      (node (ref "C18") (pin "2") (pinfunction "2_2") (pintype "passive"))
      (node (ref "CF18") (pin "3") (pinfunction "3_3") (pintype "passive"))
      (node (ref "U$1") (pin "15") (pinfunction "AINN4_15") (pintype "bidirectional"))
    )
    (net (code "44") (name "Net-(U$1-AINP1)") (class "Default")
      (node (ref "C7") (pin "2") (pinfunction "2_2") (pintype "passive"))
      (node (ref "C8") (pin "2") (pinfunction "2_2") (pintype "passive"))
      (node (ref "CF11") (pin "1") (pinfunction "1_1") (pintype "passive"))
      (node (ref "U$1") (pin "11") (pinfunction "AINP1_11") (pintype "bidirectional"))
    )
    (net (code "45") (name "Net-(U$1-AINP2)") (class "Default")
      (node (ref "C10") (pin "2") (pinfunction "2_2") (pintype "passive"))
      (node (ref "C11") (pin "2") (pinfunction "2_2") (pintype "passive"))
      (node (ref "CF13") (pin "1") (pinfunction "1_1") (pintype "passive"))
      (node (ref "U$1") (pin "18") (pinfunction "AINP2_18") (pintype "bidirectional"))
    )
    (net (code "46") (name "Net-(U$1-AINP3)") (class "Default")
      (node (ref "C13") (pin "2") (pinfunction "2_2") (pintype "passive"))
      (node (ref "C14") (pin "2") (pinfunction "2_2") (pintype "passive"))
      (node (ref "CF15") (pin "1") (pinfunction "1_1") (pintype "passive"))
      (node (ref "U$1") (pin "13") (pinfunction "AINP3_13") (pintype "bidirectional"))
    )
    (net (code "47") (name "Net-(U$1-AINP4)") (class "Default")
      (node (ref "C16") (pin "2") (pinfunction "2_2") (pintype "passive"))
      (node (ref "C17") (pin "2") (pinfunction "2_2") (pintype "passive"))
      (node (ref "CF17") (pin "1") (pinfunction "1_1") (pintype "passive"))
      (node (ref "U$1") (pin "16") (pinfunction "AINP4_16") (pintype "bidirectional"))
    )
    (net (code "48") (name "Net-(U$1-CAP1)") (class "Default")
      (node (ref "C6") (pin "1") (pinfunction "1_1") (pintype "passive"))
      (node (ref "U$1") (pin "9") (pinfunction "CAP1_9") (pintype "bidirectional"))
    )
    (net (code "49") (name "Net-(U$1-CAP2)") (class "Default")
      (node (ref "C6") (pin "2") (pinfunction "2_2") (pintype "passive"))
      (node (ref "U$1") (pin "10") (pinfunction "CAP2_10") (pintype "bidirectional"))
    )
    (net (code "50") (name "Net-(U$1-CLKIN{slash}XTAL1)") (class "Default")
      (node (ref "R1") (pin "2") (pinfunction "2_2") (pintype "passive"))
      (node (ref "TP2") (pin "TP") (pinfunction "TP_TP") (pintype "input"))
      (node (ref "U$1") (pin "3") (pinfunction "CLKIN/XTAL1_3") (pintype "bidirectional"))
    )
    (net (code "51") (name "Net-(U$1-GAIN0)") (class "Default")
      (node (ref "CF4") (pin "3") (pinfunction "3_3") (pintype "passive"))
      (node (ref "U$1") (pin "23") (pinfunction "GAIN0_23") (pintype "bidirectional"))
    )
    (net (code "52") (name "Net-(U$1-GAIN1)") (class "Default")
      (node (ref "CF5") (pin "3") (pinfunction "3_3") (pintype "passive"))
      (node (ref "U$1") (pin "24") (pinfunction "GAIN1_24") (pintype "bidirectional"))
    )
    (net (code "53") (name "Net-(U$1-REFN)") (class "Default")
      (node (ref "C3") (pin "1") (pinfunction "1_1") (pintype "passive"))
      (node (ref "C4") (pin "2") (pinfunction "2_2") (pintype "passive"))
      (node (ref "CF10") (pin "3") (pinfunction "3_3") (pintype "passive"))
      (node (ref "U$1") (pin "19") (pinfunction "REFN_19") (pintype "bidirectional"))
    )
    (net (code "54") (name "Net-(U$1-REFP)") (class "Default")
      (node (ref "C3") (pin "2") (pinfunction "2_2") (pintype "passive"))
      (node (ref "C5") (pin "2") (pinfunction "2_2") (pintype "passive"))
      (node (ref "CF9") (pin "1") (pinfunction "1_1") (pintype "passive"))
      (node (ref "U$1") (pin "20") (pinfunction "REFP_20") (pintype "bidirectional"))
    )
    (net (code "55") (name "Net-(U$1-SCLK)") (class "Default")
      (node (ref "CF2") (pin "3") (pinfunction "3_3") (pintype "passive"))
      (node (ref "U$1") (pin "27") (pinfunction "SCLK_27") (pintype "bidirectional"))
    )
    (net (code "56") (name "Net-(U$1-SPEED)") (class "Default")
      (node (ref "CF3") (pin "3") (pinfunction "3_3") (pintype "passive"))
      (node (ref "U$1") (pin "25") (pinfunction "SPEED_25") (pintype "bidirectional"))
    )
    (net (code "57") (name "Net-(U$1-~{DRDY{slash}}DOUT)") (class "Default")
      (node (ref "CF1") (pin "3") (pinfunction "3_3") (pintype "passive"))
      (node (ref "U$1") (pin "28") (pinfunction "~{DRDY/}DOUT_28") (pintype "bidirectional"))
    )
    (net (code "58") (name "Net-(U$1-~{PDWN})") (class "Default")
      (node (ref "CF6") (pin "3") (pinfunction "3_3") (pintype "passive"))
      (node (ref "U$1") (pin "26") (pinfunction "~{PDWN}_26") (pintype "bidirectional"))
    )
    (net (code "59") (name "Net-(U4A-OSC2)") (class "Default")
      (node (ref "C37") (pin "2") (pinfunction "2_2") (pintype "passive"))
      (node (ref "Q3") (pin "1") (pinfunction "1_1") (pintype "passive"))
      (node (ref "U4") (pin "7") (pinfunction "OSC2_7") (pintype "output"))
    )
    (net (code "60") (name "Net-(U5-RS)") (class "Default")
      (node (ref "R13") (pin "2") (pinfunction "2_2") (pintype "passive"))
      (node (ref "U5") (pin "8") (pinfunction "RS_8") (pintype "bidirectional"))
    )
    (net (code "61") (name "RS") (class "Default")
      (node (ref "R7") (pin "2") (pinfunction "2_2") (pintype "passive"))
      (node (ref "U4") (pin "17") (pinfunction "RESET_17") (pintype "input"))
    )
    (net (code "62") (name "RST") (class "Default")
      (node (ref "IC2") (pin "29") (pinfunction "PC6(/RESET)_29") (pintype "bidirectional"))
      (node (ref "ISP") (pin "5") (pinfunction "5_5") (pintype "passive"))
      (node (ref "R5") (pin "2") (pinfunction "2_2") (pintype "passive"))
    )
    (net (code "63") (name "SCK") (class "Default")
      (node (ref "IC2") (pin "17") (pinfunction "PB5(SCK)_17") (pintype "bidirectional"))
      (node (ref "ISP") (pin "7") (pinfunction "7_7") (pintype "passive"))
      (node (ref "U4") (pin "13") (pinfunction "SCK_13") (pintype "input"))
    )
    (net (code "64") (name "VDD") (class "Default")
      (node (ref "C1") (pin "1") (pinfunction "1_1") (pintype "passive"))
      (node (ref "C21") (pin "+") (pinfunction "+_+") (pintype "passive"))
      (node (ref "C23") (pin "1") (pinfunction "1_1") (pintype "passive"))
      (node (ref "C26") (pin "2") (pinfunction "2_2") (pintype "passive"))
      (node (ref "C27") (pin "1") (pinfunction "1_1") (pintype "passive"))
      (node (ref "C33") (pin "2") (pinfunction "2_2") (pintype "passive"))
      (node (ref "C36") (pin "2") (pinfunction "2_2") (pintype "passive"))
      (node (ref "FERRYT") (pin "1") (pinfunction "1_1") (pintype "passive"))
      (node (ref "IC1") (pin "2") (pinfunction "VO_2") (pintype "passive"))
      (node (ref "IC2") (pin "18") (pinfunction "AVCC_18") (pintype "power_in"))
      (node (ref "IC2") (pin "4") (pinfunction "VCC_4") (pintype "power_in"))
      (node (ref "IC2") (pin "6") (pinfunction "VCC_6") (pintype "power_in"))
      (node (ref "ISP") (pin "10") (pinfunction "10_10") (pintype "passive"))
      (node (ref "R5") (pin "1") (pinfunction "1_1") (pintype "passive"))
      (node (ref "R7") (pin "1") (pinfunction "1_1") (pintype "passive"))
      (node (ref "U$1") (pin "1") (pinfunction "DVDD_1") (pintype "bidirectional"))
      (node (ref "U4") (pin "18") (pinfunction "VDD_18") (pintype "power_in"))
      (node (ref "U5") (pin "3") (pinfunction "VDD_3") (pintype "power_in"))
    )
    (net (code "65") (name "unconnected-(IC2-ADC6-Pad19)") (class "Default")
      (node (ref "IC2") (pin "19") (pinfunction "ADC6_19") (pintype "bidirectional"))
    )
    (net (code "66") (name "unconnected-(IC2-ADC7-Pad22)") (class "Default")
      (node (ref "IC2") (pin "22") (pinfunction "ADC7_22") (pintype "bidirectional"))
    )
    (net (code "67") (name "unconnected-(IC2-PB0(ICP)-Pad12)") (class "Default")
      (node (ref "IC2") (pin "12") (pinfunction "PB0(ICP)_12") (pintype "bidirectional"))
    )
    (net (code "68") (name "unconnected-(IC2-PB1(OC1A)-Pad13)") (class "Default")
      (node (ref "IC2") (pin "13") (pinfunction "PB1(OC1A)_13") (pintype "bidirectional"))
    )
    (net (code "69") (name "unconnected-(IC2-PD0(RXD)-Pad30)") (class "Default")
      (node (ref "IC2") (pin "30") (pinfunction "PD0(RXD)_30") (pintype "bidirectional"))
    )
    (net (code "70") (name "unconnected-(IC2-PD4(XCK{slash}T0)-Pad2)") (class "Default")
      (node (ref "IC2") (pin "2") (pinfunction "PD4(XCK/T0)_2") (pintype "bidirectional"))
    )
    (net (code "71") (name "unconnected-(IC2-PD5(T1)-Pad9)") (class "Default")
      (node (ref "IC2") (pin "9") (pinfunction "PD5(T1)_9") (pintype "bidirectional"))
    )
    (net (code "72") (name "unconnected-(IC2-PD6(AIN0)-Pad10)") (class "Default")
      (node (ref "IC2") (pin "10") (pinfunction "PD6(AIN0)_10") (pintype "bidirectional"))
    )
    (net (code "73") (name "unconnected-(IC2-PD7(AIN1)-Pad11)") (class "Default")
      (node (ref "IC2") (pin "11") (pinfunction "PD7(AIN1)_11") (pintype "bidirectional"))
    )
    (net (code "74") (name "unconnected-(ISP-Pad3)") (class "Default")
      (node (ref "ISP") (pin "3") (pinfunction "3_3") (pintype "passive"))
    )
    (net (code "75") (name "unconnected-(ISP-Pad4)") (class "Default")
      (node (ref "ISP") (pin "4") (pinfunction "4_4") (pintype "passive"))
    )
    (net (code "76") (name "unconnected-(ISP-Pad6)") (class "Default")
      (node (ref "ISP") (pin "6") (pinfunction "6_6") (pintype "passive"))
    )
    (net (code "77") (name "unconnected-(ISP-Pad8)") (class "Default")
      (node (ref "ISP") (pin "8") (pinfunction "8_8") (pintype "passive"))
    )
    (net (code "78") (name "unconnected-(U$1-XTAL2-Pad4)") (class "Default")
      (node (ref "U$1") (pin "4") (pinfunction "XTAL2_4") (pintype "bidirectional"))
    )
    (net (code "79") (name "unconnected-(U4A-CLKOUT-Pad3)") (class "Default")
      (node (ref "U4") (pin "3") (pinfunction "CLKOUT_3") (pintype "output"))
    )
    (net (code "80") (name "unconnected-(U4A-RX0BF-Pad11)") (class "Default")
      (node (ref "U4") (pin "11") (pinfunction "RX0BF_11") (pintype "output"))
    )
    (net (code "81") (name "unconnected-(U4A-RX1BF-Pad10)") (class "Default")
      (node (ref "U4") (pin "10") (pinfunction "RX1BF_10") (pintype "output"))
    )
    (net (code "82") (name "unconnected-(U4A-TX0RTS-Pad4)") (class "Default")
      (node (ref "U4") (pin "4") (pinfunction "TX0RTS_4") (pintype "input"))
    )
    (net (code "83") (name "unconnected-(U4A-TX1RTS-Pad5)") (class "Default")
      (node (ref "U4") (pin "5") (pinfunction "TX1RTS_5") (pintype "input"))
    )
    (net (code "84") (name "unconnected-(U4A-TX2RTS-Pad6)") (class "Default")
      (node (ref "U4") (pin "6") (pinfunction "TX2RTS_6") (pintype "input"))
    )
    (net (code "85") (name "unconnected-(U5-VREF-Pad5)") (class "Default")
      (node (ref "U5") (pin "5") (pinfunction "VREF_5") (pintype "bidirectional"))
    )
  )
)
